# Module-POWER.net
KiCad netlist of a schematic drawn in Altium Designer
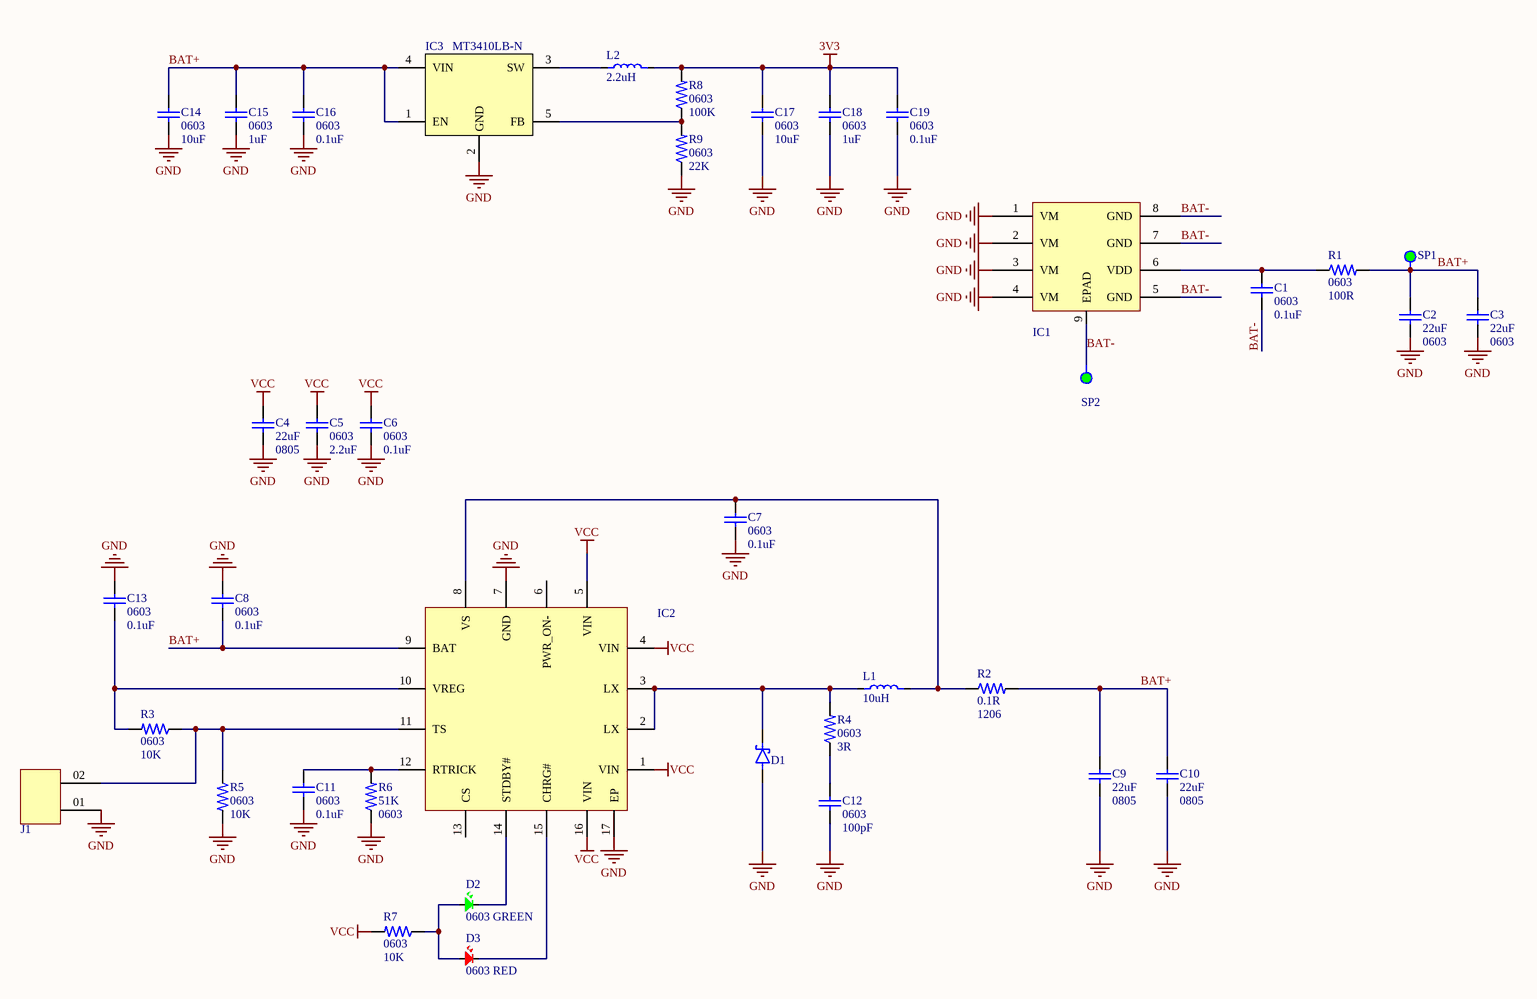
[diagram p0: Module-POWER.SchDoc]

(export (version "E")
  (design (tool "Eeschema 10.0.6"))
  (components
    (comp (ref "C1")
      (value "0.1uF")
      (footprint "SMD-CAP-0603-YAGEO")
      (description "0603 0.1 uF 16 V ±10 % Tolerance X7R SMT Multilayer Ceramic Capacitor")
      (fields
        (field (name "MANUFACTURER") "Yageo")
        (field (name "MANUFACTURER PART NUMBER") "CC0603KRX7R7BB104")
        (field (name "PACKAGE") "0603")
        (field (name "DESIGNER") "TVBac")
      )
      (libsource (lib "Capacitors") (part "CAP; 0.1uF; 16V; 0603; SMD; CC0603KRX7R7BB104"))
    )
    (comp (ref "C2")
      (value "22uF")
      (footprint "SMD-CAP-0603-YAGEO")
      (description "Multilayer Ceramic Capacitor, 22 uF, 10 V, ï¿½ 20%, X5R, 0603 [1608 Metric]")
      (fields
        (field (name "MANUFACTURER") "Yageo")
        (field (name "MANUFACTURER PART NUMBER") "CC0603MRX5R6BB226")
        (field (name "PACKAGE") "0603")
        (field (name "DESIGNER") "TVBac")
      )
      (libsource (lib "Capacitors") (part "CAP; 22uF; 25V; SMD; CC0603MRX5R6BB226"))
    )
    (comp (ref "C3")
      (value "22uF")
      (footprint "SMD-CAP-0603-YAGEO")
      (description "Multilayer Ceramic Capacitor, 22 uF, 10 V, ï¿½ 20%, X5R, 0603 [1608 Metric]")
      (fields
        (field (name "MANUFACTURER") "Yageo")
        (field (name "MANUFACTURER PART NUMBER") "CC0603MRX5R6BB226")
        (field (name "PACKAGE") "0603")
        (field (name "DESIGNER") "TVBac")
      )
      (libsource (lib "Capacitors") (part "CAP; 22uF; 25V; SMD; CC0603MRX5R6BB226"))
    )
    (comp (ref "C4")
      (value "22uF")
      (footprint "SMD-CAP-0805-YAGEO")
      (fields
        (field (name "MANUFACTURER") "Yageo")
        (field (name "MANUFACTURER PART NUMBER") "CC0805MKX5R8BB226")
        (field (name "PACKAGE") "0805")
        (field (name "Comment") "22 µF ±20% 25V Ceramic Capacitor X5R 0805 (2012 Metric)")
      )
      (libsource (lib "Capacitors") (part "CAP; 22uF; 0805; 25V; SMD; CC0805MKX5R8BB226"))
    )
    (comp (ref "C5")
      (value "2.2uF")
      (footprint "SMD-CAP-0603-YAGEO")
      (description "0603 2.2 uF 25 V ±10% Tolerance X5R SMT Multilayer Ceramic Capacitor")
      (fields
        (field (name "MANUFACTURER") "Yageo")
        (field (name "MANUFACTURER PART NUMBER") "CC0603KRX5R8BB225")
        (field (name "PACKAGE") "0603")
        (field (name "DESIGNER") "TVBac")
      )
      (libsource (lib "Capacitors") (part "CAP; 2.2uF; 25V; SMD; 0603; CC0603KRX5R8BB225"))
    )
    (comp (ref "C6")
      (value "0.1uF")
      (footprint "SMD-CAP-0603-YAGEO")
      (description "Multilayer Ceramic Capacitors MLCC - SMD/SMT 100V 0.1uF X7R 0603 10%")
      (fields
        (field (name "MANUFACTURER") "Yageo")
        (field (name "MANUFACTURER PART NUMBER") "CC0603KRX7R0BB104")
        (field (name "PACKAGE") "0603")
        (field (name "DESIGNER") "TVBac")
      )
      (libsource (lib "Capacitors") (part "CAP; 0.1uF; 100V; 0603; SMD; CC0603KRX7R0BB104"))
    )
    (comp (ref "C7")
      (value "0.1uF")
      (footprint "SMD-CAP-0603-YAGEO")
      (description "Multilayer Ceramic Capacitors MLCC - SMD/SMT 100V 0.1uF X7R 0603 10%")
      (fields
        (field (name "MANUFACTURER") "Yageo")
        (field (name "MANUFACTURER PART NUMBER") "CC0603KRX7R0BB104")
        (field (name "PACKAGE") "0603")
        (field (name "DESIGNER") "TVBac")
      )
      (libsource (lib "Capacitors") (part "CAP; 0.1uF; 100V; 0603; SMD; CC0603KRX7R0BB104"))
    )
    (comp (ref "C8")
      (value "0.1uF")
      (footprint "SMD-CAP-0603-YAGEO")
      (description "Multilayer Ceramic Capacitors MLCC - SMD/SMT 100V 0.1uF X7R 0603 10%")
      (fields
        (field (name "MANUFACTURER") "Yageo")
        (field (name "MANUFACTURER PART NUMBER") "CC0603KRX7R0BB104")
        (field (name "PACKAGE") "0603")
        (field (name "DESIGNER") "TVBac")
      )
      (libsource (lib "Capacitors") (part "CAP; 0.1uF; 100V; 0603; SMD; CC0603KRX7R0BB104"))
    )
    (comp (ref "C9")
      (value "22uF")
      (footprint "SMD-CAP-0805-YAGEO")
      (fields
        (field (name "MANUFACTURER") "Yageo")
        (field (name "MANUFACTURER PART NUMBER") "CC0805MKX5R8BB226")
        (field (name "PACKAGE") "0805")
        (field (name "Comment") "22 µF ±20% 25V Ceramic Capacitor X5R 0805 (2012 Metric)")
      )
      (libsource (lib "Capacitors") (part "CAP; 22uF; 0805; 25V; SMD; CC0805MKX5R8BB226"))
    )
    (comp (ref "C10")
      (value "22uF")
      (footprint "SMD-CAP-0805-YAGEO")
      (fields
        (field (name "MANUFACTURER") "Yageo")
        (field (name "MANUFACTURER PART NUMBER") "CC0805MKX5R8BB226")
        (field (name "PACKAGE") "0805")
        (field (name "Comment") "22 µF ±20% 25V Ceramic Capacitor X5R 0805 (2012 Metric)")
      )
      (libsource (lib "Capacitors") (part "CAP; 22uF; 0805; 25V; SMD; CC0805MKX5R8BB226"))
    )
    (comp (ref "C11")
      (value "0.1uF")
      (footprint "SMD-CAP-0603-YAGEO")
      (description "Multilayer Ceramic Capacitors MLCC - SMD/SMT 100V 0.1uF X7R 0603 10%")
      (fields
        (field (name "MANUFACTURER") "Yageo")
        (field (name "MANUFACTURER PART NUMBER") "CC0603KRX7R0BB104")
        (field (name "PACKAGE") "0603")
        (field (name "DESIGNER") "TVBac")
      )
      (libsource (lib "Capacitors") (part "CAP; 0.1uF; 100V; 0603; SMD; CC0603KRX7R0BB104"))
    )
    (comp (ref "C12")
      (value "100pF")
      (footprint "SMD-CAP-0603-YAGEO")
      (description "0603 100 pF 50 V ±5 % Tolerance NP0 SMT Multilayer Ceramic Capacitor")
      (fields
        (field (name "MANUFACTURER") "Yageo")
        (field (name "MANUFACTURER PART NUMBER") "CC0603JRNPO9BN101")
        (field (name "PACKAGE") "0603")
      )
      (libsource (lib "Capacitors") (part "CAP; 100pF; 0603; SMD; CC0603JRNPO9BN101"))
    )
    (comp (ref "C13")
      (value "0.1uF")
      (footprint "SMD-CAP-0603-YAGEO")
      (description "Multilayer Ceramic Capacitors MLCC - SMD/SMT 100V 0.1uF X7R 0603 10%")
      (fields
        (field (name "MANUFACTURER") "Yageo")
        (field (name "MANUFACTURER PART NUMBER") "CC0603KRX7R0BB104")
        (field (name "PACKAGE") "0603")
        (field (name "DESIGNER") "TVBac")
      )
      (libsource (lib "Capacitors") (part "CAP; 0.1uF; 100V; 0603; SMD; CC0603KRX7R0BB104"))
    )
    (comp (ref "C14")
      (value "10uF")
      (footprint "SMD-CAP-0603-YAGEO")
      (description "Multilayer Ceramic Capacitor, 10 uF, 25 V, ï¿½ 20%, X5R, 0603 [1608 Metric]")
      (fields
        (field (name "MANUFACTURER") "Yageo")
        (field (name "MANUFACTURER PART NUMBER") "CC0603MRX5R8BB106")
        (field (name "PACKAGE") "0603")
        (field (name "DESIGNER") "TVBac")
      )
      (libsource (lib "Capacitors") (part "CAP; 10uF; 25V; SMD; 0603; CC0603MRX5R8BB106"))
    )
    (comp (ref "C15")
      (value "1uF")
      (footprint "SMD-CAP-0603-YAGEO")
      (description "Surface Mount Ceramic Multilayer Capacitor 1uF -20% to 80% Y5V 10V 0603 Paper T/R")
      (fields
        (field (name "MANUFACTURER") "Yageo")
        (field (name "MANUFACTURER PART NUMBER") "CC0603ZRY5V6BB105")
        (field (name "PACKAGE") "0603")
        (field (name "DESIGNER") "TVBac")
      )
      (libsource (lib "Capacitors") (part "CAP; 1uF; 10V; 0603; SMD; CC0603ZRY5V6BB105"))
    )
    (comp (ref "C16")
      (value "0.1uF")
      (footprint "SMD-CAP-0603-YAGEO")
      (description "0603 0.1 uF 16 V ±10 % Tolerance X7R SMT Multilayer Ceramic Capacitor")
      (fields
        (field (name "MANUFACTURER") "Yageo")
        (field (name "MANUFACTURER PART NUMBER") "CC0603KRX7R7BB104")
        (field (name "PACKAGE") "0603")
        (field (name "DESIGNER") "TVBac")
      )
      (libsource (lib "Capacitors") (part "CAP; 0.1uF; 16V; 0603; SMD; CC0603KRX7R7BB104"))
    )
    (comp (ref "C17")
      (value "10uF")
      (footprint "SMD-CAP-0603-YAGEO")
      (description "Multilayer Ceramic Capacitor, 10 uF, 25 V, ï¿½ 20%, X5R, 0603 [1608 Metric]")
      (fields
        (field (name "MANUFACTURER") "Yageo")
        (field (name "MANUFACTURER PART NUMBER") "CC0603MRX5R8BB106")
        (field (name "PACKAGE") "0603")
        (field (name "DESIGNER") "TVBac")
      )
      (libsource (lib "Capacitors") (part "CAP; 10uF; 25V; SMD; 0603; CC0603MRX5R8BB106"))
    )
    (comp (ref "C18")
      (value "1uF")
      (footprint "SMD-CAP-0603-YAGEO")
      (description "Surface Mount Ceramic Multilayer Capacitor 1uF -20% to 80% Y5V 10V 0603 Paper T/R")
      (fields
        (field (name "MANUFACTURER") "Yageo")
        (field (name "MANUFACTURER PART NUMBER") "CC0603ZRY5V6BB105")
        (field (name "PACKAGE") "0603")
        (field (name "DESIGNER") "TVBac")
      )
      (libsource (lib "Capacitors") (part "CAP; 1uF; 10V; 0603; SMD; CC0603ZRY5V6BB105"))
    )
    (comp (ref "C19")
      (value "0.1uF")
      (footprint "SMD-CAP-0603-YAGEO")
      (description "0603 0.1 uF 16 V ±10 % Tolerance X7R SMT Multilayer Ceramic Capacitor")
      (fields
        (field (name "MANUFACTURER") "Yageo")
        (field (name "MANUFACTURER PART NUMBER") "CC0603KRX7R7BB104")
        (field (name "PACKAGE") "0603")
        (field (name "DESIGNER") "TVBac")
      )
      (libsource (lib "Capacitors") (part "CAP; 0.1uF; 16V; 0603; SMD; CC0603KRX7R7BB104"))
    )
    (comp (ref "D1")
      (value "Diode 40 V 3A Surface Mount DO-214AC (SMA)")
      (footprint "SMD-DO-214AC-214-CT")
      (description "Diode Schottky Si 40V 3A 2-Pin SMA T/R")
      (fields
        (field (name "MANUFACTURER") "Comchip")
        (field (name "MANUFACTURER PART NUMBER") "SS34-HF")
        (field (name "DESIGNER") "TVBac")
      )
      (libsource (lib "Diode") (part "DIODE; SMD; SCHOTTKY; SS34-HF"))
    )
    (comp (ref "D2")
      (value "0603 GREEN")
      (footprint "LED0603_GREEN")
      (fields
        (field (name "MANUFACTURER") "Amicc")
        (field (name "MANUFACTURE PART NUMBER") "A-SP192DGHC-C01-4T")
      )
      (libsource (lib "LED") (part "L0603_GREEN"))
    )
    (comp (ref "D3")
      (value "0603 RED")
      (footprint "LED0603_RED")
      (fields
        (field (name "MANUFACTURER") "XINGLIGHT")
        (field (name "MANUFACTURE PART NUMBER") "XL-1608SURC-06")
      )
      (libsource (lib "LED") (part "L0603_RED"))
    )
    (comp (ref "IC1") (value "XB8089D") (footprint "SOIC-8-XB8089D") (libsource (lib "IC") (part "XB8089D")))
    (comp (ref "IC2")
      (value "5V~12V Lithium-ion/Polymer 1~2 2A TQFN-16-EP(4x4) Battery Management ROHS")
      (footprint "TQFN-16 - TP5100")
      (libsource (lib "IC") (part "TP5100"))
    )
    (comp (ref "IC3")
      (value "MT3410LB-N")
      (footprint "SOT23-5-MT3410")
      (description "SOT-23-5 DC-DC Converters ROHS")
      (fields (field (name "MANUFACTURER") "XI'AN Aerosemi Tech") (field (name "LCSC PART") "C42420805"))
      (libsource (lib "IC") (part "MT3410LB-N"))
    )
    (comp (ref "J1")
      (value "Connector Header Through Hole 2 position")
      (footprint "HEADER-2.54-2")
      (description "Headers & Wire Housings Classic PCB Header Strips, 0.100 pitch")
      (fields
        (field (name "MANUFACTURER") "Samtec")
        (field (name "MANUFACTURER PART NUMBER") "TSW-101-15-T-D")
        (field (name "DESIGNER") "TVBac")
      )
      (libsource (lib "Socket") (part "HEADER; 2PIN; 2.54; VER; TSW-101-15-T-D"))
    )
    (comp (ref "L1")
      (value "10uH")
      (footprint "SMD-HxLxW-4.5x6.5x6.0-PEC")
      (description "Power Choke Shielded Wirewound 10uH 20% 100KHz Metal 3.7A 0.0748Ohm DCR Automotive T/R")
      (fields
        (field (name "MANUFACTURER") "Panasonic")
        (field (name "MANUFACTURER PART NUMBER") "ETQ-P3M100HFN")
      )
      (libsource (lib "Inductors") (part "IND; 10uH; 3.7A; ETQ-P3M100HFN"))
    )
    (comp (ref "L2")
      (value "2.2uH")
      (footprint "SMD-HxLxW-3.0x5.5x5.0-PEC")
      (description "Ind Power Shielded Wirewound 2.2uH 20% 100KHz Metal 6.3A (5.5 X 5 X 3mm) Emboss T/R")
      (fields
        (field (name "MANUFACTURER") "Panasonic")
        (field (name "MANUFACTURER PART NUMBER") "ETQ-P3M2R2KVP")
        (field (name "DESIGNER") "TVBac")
      )
      (libsource (lib "Inductors") (part "IND; 2.2uH; SMD; 6.3A; ETQ-P3M2R2KVP"))
    )
    (comp (ref "R1")
      (value "100R")
      (footprint "SMD-RES-0603-RS")
      (description "Res Thick Film 0603 100 Ohm 1% 0.1W(1/10W) ±100ppm/C Pad SMD T/R Automotive AEC-Q200")
      (fields
        (field (name "MANUFACTURER") "Rohm")
        (field (name "MANUFACTURER PART NUMBER") "KTR03EZPF1000")
        (field (name "PACKAGE") "0603")
        (field (name "DESIGNER") "TVBac")
      )
      (libsource (lib "Resistors") (part "RES; 100R; 0603; SMD; KTR03EZPF1000"))
    )
    (comp (ref "R2")
      (value "0.1R")
      (footprint "SMD-RES-1206-YAGEO")
      (description "SMD Chip Resistor, 100 MOhm, ± 5%, 250 mW, 1206 [3216 Metric], Thick Film, Low Ohmic")
      (fields
        (field (name "MANUFACTURER") "Yageo")
        (field (name "MANUFACTURER PART NUMBER") "RL1206JR-070R1L")
        (field (name "PACKAGE") "1206")
      )
      (libsource (lib "Resistors") (part "RES; 0.1R; 1206; SMD; RL1206JR-070R1L"))
    )
    (comp (ref "R3")
      (value "10K")
      (footprint "SMD-RES-0603-YAGEO")
      (description "SMD Chip Resistor, 10 Kohm, ½ 1%, 100 Mw, 0603 [1608 Metric], Thick Film, General Purpose")
      (fields
        (field (name "MANUFACTURER") "Yageo")
        (field (name "MANUFACTURER PART NUMBER") "RC0603FR-0710KL")
        (field (name "PACKAGE") "0603")
      )
      (libsource (lib "Resistors") (part "RES; 10K; 0603; SMD; RC0603FR-0710KL"))
    )
    (comp (ref "R4")
      (value "3R")
      (footprint "SMD-RES-0603-YAGEO")
      (description "Thin Film Res 0603 3 Ohm 1% 0.1W(1/10W) 50ppm/C Epoxy Pad SMD T/R")
      (fields
        (field (name "MANUFACTURER") "Yageo")
        (field (name "MANUFACTURER PART NUMBER") "RT0603FRE073RL")
        (field (name "PACKAGE") "0603")
      )
      (libsource (lib "Resistors") (part "RES; 3R; 0603; SMD; RT0603FRE073RL"))
    )
    (comp (ref "R5")
      (value "10K")
      (footprint "SMD-RES-0603-YAGEO")
      (description "SMD Chip Resistor, 10 Kohm, ½ 1%, 100 Mw, 0603 [1608 Metric], Thick Film, General Purpose")
      (fields
        (field (name "MANUFACTURER") "Yageo")
        (field (name "MANUFACTURER PART NUMBER") "RC0603FR-0710KL")
        (field (name "PACKAGE") "0603")
      )
      (libsource (lib "Resistors") (part "RES; 10K; 0603; SMD; RC0603FR-0710KL"))
    )
    (comp (ref "R6")
      (value "51K")
      (footprint "SMD-RES-0603-YAGEO")
      (description "SMD Chip Resistor, 510 Kohm, ½ 1%, 100 Mw, 0603 [1608 Metric], Thick Film, General Purpose")
      (fields
        (field (name "MANUFACTURER") "Yageo")
        (field (name "MANUFACTURER PART NUMBER") "RC0603FR-07510KL")
        (field (name "PACKAGE") "0603")
      )
      (libsource (lib "Resistors") (part "RES; 51K; 0603; SMD; RC0603FR-07510KL"))
    )
    (comp (ref "R7")
      (value "10K")
      (footprint "SMD-RES-0603-YAGEO")
      (description "SMD Chip Resistor, 10 Kohm, ½ 1%, 100 Mw, 0603 [1608 Metric], Thick Film, General Purpose")
      (fields
        (field (name "MANUFACTURER") "Yageo")
        (field (name "MANUFACTURER PART NUMBER") "RC0603FR-0710KL")
        (field (name "PACKAGE") "0603")
      )
      (libsource (lib "Resistors") (part "RES; 10K; 0603; SMD; RC0603FR-0710KL"))
    )
    (comp (ref "R8")
      (value "100K")
      (footprint "SMD-RES-0603-YAGEO")
      (description "SMD Chip Resistor, 100 kOhm, ï¿½ 1%, 100 mW, 0603 [1608 Metric], Thick Film, General Purpose")
      (fields
        (field (name "MANUFACTURER") "Yageo")
        (field (name "TOLERANCE") "1%")
        (field (name "PACKAGE") "0603")
      )
      (libsource (lib "Resistors") (part "RES; 100K; 0603; SMD; RC0603FR-07100KL"))
    )
    (comp (ref "R9")
      (value "22K")
      (footprint "SMD-RES-0603-YAGEO")
      (description "SMD Chip Resistor 22 Kohm ½ 1% 100 Mw 0603 [1608 Metric] Thick Film General Purpose")
      (fields
        (field (name "MANUFACTURER") "Yageo")
        (field (name "MANUFACTURER PART NUMBER") "RC0603FR-0722KL")
        (field (name "PACKAGE") "0603")
      )
      (libsource (lib "Resistors") (part "RES; 22K; 0603; SMD; RC0603FR-0722KL"))
    )
    (comp (ref "SP1")
      (value "SP")
      (footprint "SOLDERING PAD BIG 3")
      (description "Soldering Pad")
      (libsource (lib "Socket") (part "SOLDERING PAD"))
    )
    (comp (ref "SP2")
      (value "SP")
      (footprint "SOLDERING PAD BIG 3")
      (description "Soldering Pad")
      (libsource (lib "Socket") (part "SOLDERING PAD"))
    )
  )
  (nets
    (net (code "1") (name "/BAT+") (class "Default")
      (node (ref "C10") (pin "2") (pinfunction "2_2") (pintype "passive"))
      (node (ref "C14") (pin "2") (pinfunction "2_2") (pintype "passive"))
      (node (ref "C15") (pin "2") (pinfunction "2_2") (pintype "passive"))
      (node (ref "C16") (pin "2") (pinfunction "2_2") (pintype "passive"))
      (node (ref "C2") (pin "1") (pinfunction "1_1") (pintype "passive"))
      (node (ref "C3") (pin "2") (pinfunction "2_2") (pintype "passive"))
      (node (ref "C8") (pin "2") (pinfunction "2_2") (pintype "passive"))
      (node (ref "C9") (pin "2") (pinfunction "2_2") (pintype "passive"))
      (node (ref "IC2") (pin "9") (pinfunction "BAT_9") (pintype "passive"))
      (node (ref "IC3") (pin "1") (pinfunction "EN_1") (pintype "passive"))
      (node (ref "IC3") (pin "4") (pinfunction "VIN_4") (pintype "passive"))
      (node (ref "R1") (pin "2") (pinfunction "2_2") (pintype "passive"))
      (node (ref "R2") (pin "2") (pinfunction "2_2") (pintype "passive"))
      (node (ref "SP1") (pin "1") (pinfunction "1_1") (pintype "passive"))
    )
    (net (code "2") (name "/BAT-") (class "Default")
      (node (ref "C1") (pin "1") (pinfunction "1_1") (pintype "passive"))
      (node (ref "IC1") (pin "5") (pinfunction "GND_5") (pintype "passive"))
      (node (ref "IC1") (pin "7") (pinfunction "GND_7") (pintype "passive"))
      (node (ref "IC1") (pin "8") (pinfunction "GND_8") (pintype "passive"))
      (node (ref "IC1") (pin "9") (pinfunction "EPAD_9") (pintype "passive"))
      (node (ref "SP2") (pin "1") (pinfunction "1_1") (pintype "passive"))
    )
    (net (code "3") (name "3V3") (class "Default")
      (node (ref "C17") (pin "2") (pinfunction "2_2") (pintype "passive"))
      (node (ref "C18") (pin "2") (pinfunction "2_2") (pintype "passive"))
      (node (ref "C19") (pin "2") (pinfunction "2_2") (pintype "passive"))
      (node (ref "L2") (pin "2") (pinfunction "2_2") (pintype "passive"))
      (node (ref "R8") (pin "2") (pinfunction "2_2") (pintype "passive"))
    )
    (net (code "4") (name "GND") (class "Default")
      (node (ref "C10") (pin "1") (pinfunction "1_1") (pintype "passive"))
      (node (ref "C11") (pin "1") (pinfunction "1_1") (pintype "passive"))
      (node (ref "C12") (pin "1") (pinfunction "1_1") (pintype "passive"))
      (node (ref "C13") (pin "1") (pinfunction "1_1") (pintype "passive"))
      (node (ref "C14") (pin "1") (pinfunction "1_1") (pintype "passive"))
      (node (ref "C15") (pin "1") (pinfunction "1_1") (pintype "passive"))
      (node (ref "C16") (pin "1") (pinfunction "1_1") (pintype "passive"))
      (node (ref "C17") (pin "1") (pinfunction "1_1") (pintype "passive"))
      (node (ref "C18") (pin "1") (pinfunction "1_1") (pintype "passive"))
      (node (ref "C19") (pin "1") (pinfunction "1_1") (pintype "passive"))
      (node (ref "C2") (pin "2") (pinfunction "2_2") (pintype "passive"))
      (node (ref "C3") (pin "1") (pinfunction "1_1") (pintype "passive"))
      (node (ref "C4") (pin "1") (pinfunction "1_1") (pintype "passive"))
      (node (ref "C5") (pin "1") (pinfunction "1_1") (pintype "passive"))
      (node (ref "C6") (pin "1") (pinfunction "1_1") (pintype "passive"))
      (node (ref "C7") (pin "1") (pinfunction "1_1") (pintype "passive"))
      (node (ref "C8") (pin "1") (pinfunction "1_1") (pintype "passive"))
      (node (ref "C9") (pin "1") (pinfunction "1_1") (pintype "passive"))
      (node (ref "D1") (pin "2") (pinfunction "A_2") (pintype "passive"))
      (node (ref "IC1") (pin "1") (pinfunction "VM_1") (pintype "passive"))
      (node (ref "IC1") (pin "2") (pinfunction "VM_2") (pintype "passive"))
      (node (ref "IC1") (pin "3") (pinfunction "VM_3") (pintype "passive"))
      (node (ref "IC1") (pin "4") (pinfunction "VM_4") (pintype "passive"))
      (node (ref "IC2") (pin "17") (pinfunction "EP_17") (pintype "passive"))
      (node (ref "IC2") (pin "7") (pinfunction "GND_7") (pintype "passive"))
      (node (ref "IC3") (pin "2") (pinfunction "GND_2") (pintype "passive"))
      (node (ref "J1") (pin "01") (pinfunction "1_01") (pintype "passive"))
      (node (ref "R5") (pin "2") (pinfunction "2_2") (pintype "passive"))
      (node (ref "R6") (pin "1") (pinfunction "1_1") (pintype "passive"))
      (node (ref "R9") (pin "1") (pinfunction "1_1") (pintype "passive"))
    )
    (net (code "5") (name "Net-(C12-Pad2)") (class "Default")
      (node (ref "C12") (pin "2") (pinfunction "2_2") (pintype "passive"))
      (node (ref "R4") (pin "1") (pinfunction "1_1") (pintype "passive"))
    )
    (net (code "6") (name "Net-(D1-K)") (class "Default")
      (node (ref "D1") (pin "1") (pinfunction "K_1") (pintype "passive"))
      (node (ref "IC2") (pin "2") (pinfunction "LX_2") (pintype "passive"))
      (node (ref "IC2") (pin "3") (pinfunction "LX_3") (pintype "passive"))
      (node (ref "L1") (pin "1") (pinfunction "1_1") (pintype "passive"))
      (node (ref "R4") (pin "2") (pinfunction "2_2") (pintype "passive"))
    )
    (net (code "7") (name "Net-(D2-Pad1)") (class "Default")
      (node (ref "D2") (pin "1") (pinfunction "1_1") (pintype "passive"))
      (node (ref "D3") (pin "1") (pinfunction "1_1") (pintype "passive"))
      (node (ref "R7") (pin "1") (pinfunction "1_1") (pintype "passive"))
    )
    (net (code "8") (name "Net-(IC1-VDD)") (class "Default")
      (node (ref "C1") (pin "2") (pinfunction "2_2") (pintype "passive"))
      (node (ref "IC1") (pin "6") (pinfunction "VDD_6") (pintype "passive"))
      (node (ref "R1") (pin "1") (pinfunction "1_1") (pintype "passive"))
    )
    (net (code "9") (name "Net-(IC2-CHRG#)") (class "Default")
      (node (ref "D3") (pin "2") (pinfunction "2_2") (pintype "passive"))
      (node (ref "IC2") (pin "15") (pinfunction "CHRG#_15") (pintype "passive"))
    )
    (net (code "10") (name "Net-(IC2-RTRICK)") (class "Default")
      (node (ref "C11") (pin "2") (pinfunction "2_2") (pintype "passive"))
      (node (ref "IC2") (pin "12") (pinfunction "RTRICK_12") (pintype "passive"))
      (node (ref "R6") (pin "2") (pinfunction "2_2") (pintype "passive"))
    )
    (net (code "11") (name "Net-(IC2-STDBY#)") (class "Default")
      (node (ref "D2") (pin "2") (pinfunction "2_2") (pintype "passive"))
      (node (ref "IC2") (pin "14") (pinfunction "STDBY#_14") (pintype "passive"))
    )
    (net (code "12") (name "Net-(IC2-TS)") (class "Default")
      (node (ref "IC2") (pin "11") (pinfunction "TS_11") (pintype "passive"))
      (node (ref "J1") (pin "02") (pinfunction "2_02") (pintype "passive"))
      (node (ref "R3") (pin "1") (pinfunction "1_1") (pintype "passive"))
      (node (ref "R5") (pin "1") (pinfunction "1_1") (pintype "passive"))
    )
    (net (code "13") (name "Net-(IC2-VREG)") (class "Default")
      (node (ref "C13") (pin "2") (pinfunction "2_2") (pintype "passive"))
      (node (ref "IC2") (pin "10") (pinfunction "VREG_10") (pintype "passive"))
      (node (ref "R3") (pin "2") (pinfunction "2_2") (pintype "passive"))
    )
    (net (code "14") (name "Net-(IC2-VS)") (class "Default")
      (node (ref "C7") (pin "2") (pinfunction "2_2") (pintype "passive"))
      (node (ref "IC2") (pin "8") (pinfunction "VS_8") (pintype "passive"))
      (node (ref "L1") (pin "2") (pinfunction "2_2") (pintype "passive"))
      (node (ref "R2") (pin "1") (pinfunction "1_1") (pintype "passive"))
    )
    (net (code "15") (name "Net-(IC3-FB)") (class "Default")
      (node (ref "IC3") (pin "5") (pinfunction "FB_5") (pintype "passive"))
      (node (ref "R8") (pin "1") (pinfunction "1_1") (pintype "passive"))
      (node (ref "R9") (pin "2") (pinfunction "2_2") (pintype "passive"))
    )
    (net (code "16") (name "Net-(IC3-SW)") (class "Default")
      (node (ref "IC3") (pin "3") (pinfunction "SW_3") (pintype "passive"))
      (node (ref "L2") (pin "1") (pinfunction "1_1") (pintype "passive"))
    )
    (net (code "17") (name "VCC") (class "Default")
      (node (ref "C4") (pin "2") (pinfunction "2_2") (pintype "passive"))
      (node (ref "C5") (pin "2") (pinfunction "2_2") (pintype "passive"))
      (node (ref "C6") (pin "2") (pinfunction "2_2") (pintype "passive"))
      (node (ref "IC2") (pin "1") (pinfunction "VIN_1") (pintype "passive"))
      (node (ref "IC2") (pin "16") (pinfunction "VIN_16") (pintype "passive"))
      (node (ref "IC2") (pin "4") (pinfunction "VIN_4") (pintype "passive"))
      (node (ref "IC2") (pin "5") (pinfunction "VIN_5") (pintype "passive"))
      (node (ref "R7") (pin "2") (pinfunction "2_2") (pintype "passive"))
    )
    (net (code "18") (name "unconnected-(IC2-CS-Pad13)") (class "Default")
      (node (ref "IC2") (pin "13") (pinfunction "CS_13") (pintype "passive"))
    )
    (net (code "19") (name "unconnected-(IC2-PWR_ON--Pad6)") (class "Default")
      (node (ref "IC2") (pin "6") (pinfunction "PWR_ON-_6") (pintype "passive"))
    )
  )
)
